# SCH_Creality_k1c_2026-01-29.net
KiCad netlist of a schematic drawn in EasyEDA
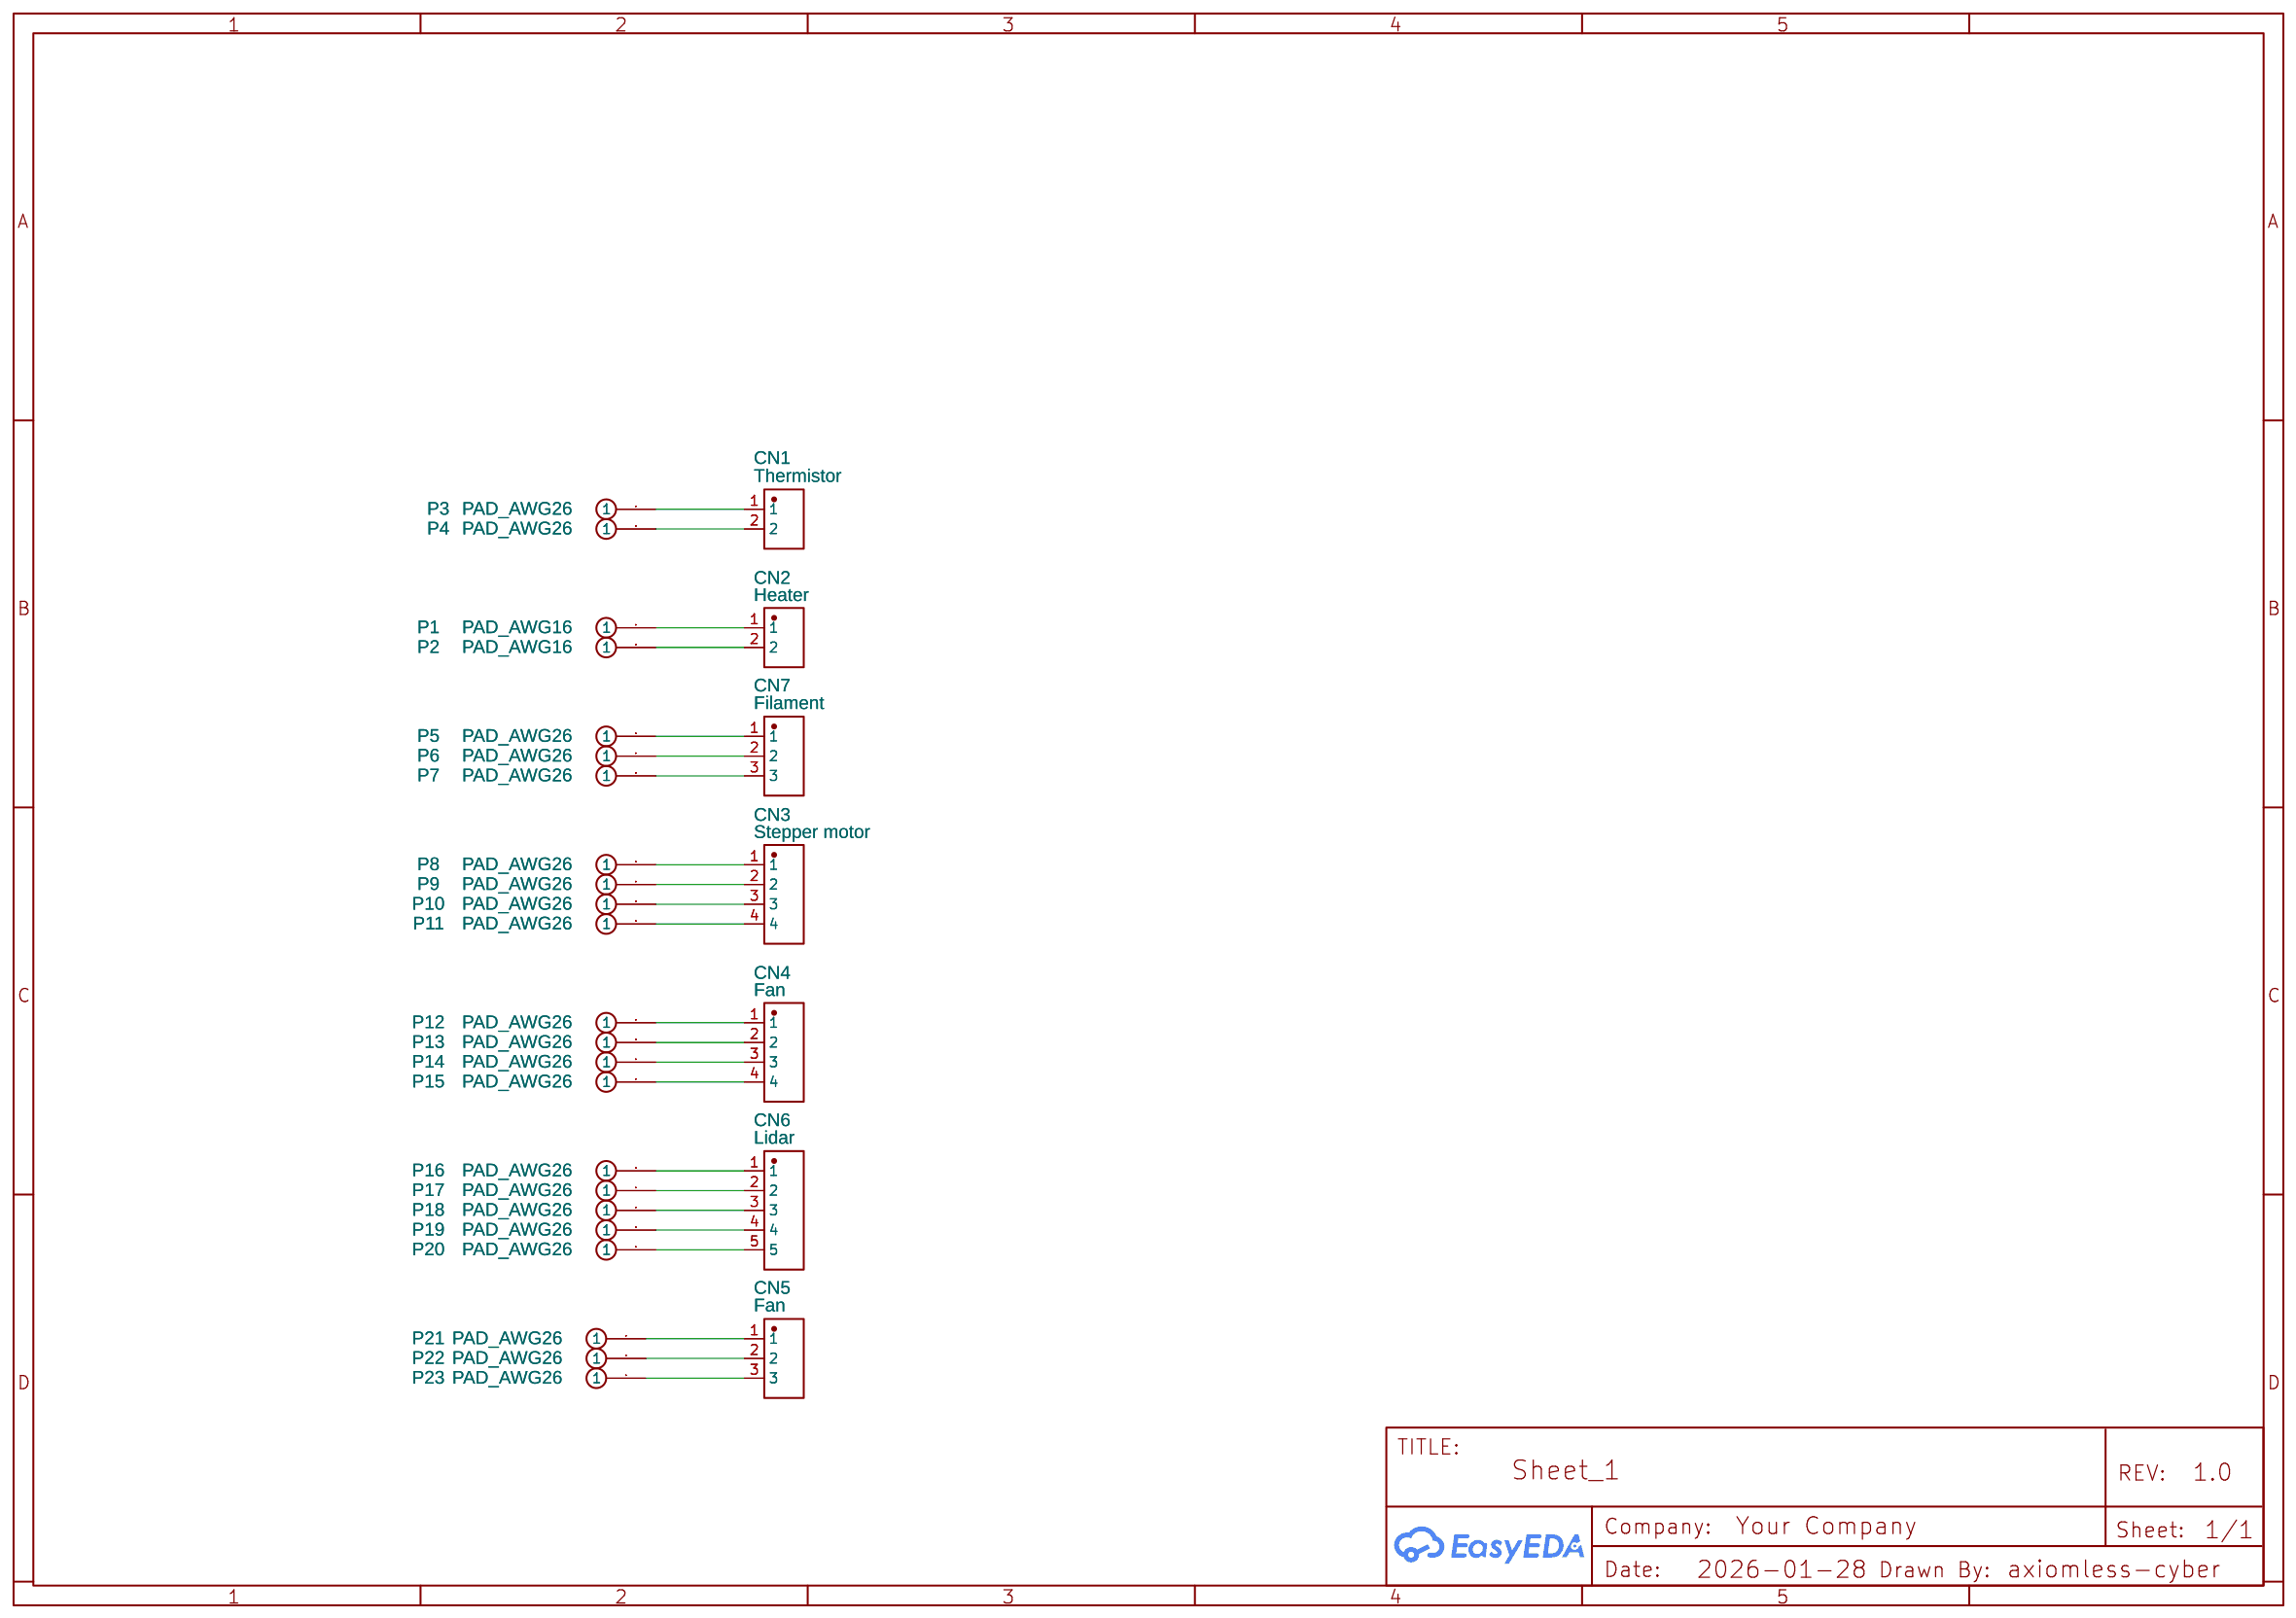
[diagram p0: schematic sheet]

(export (version "E")
  (design (tool "Eeschema 10.0.6"))
  (components
    (comp (ref "CN1")
      (value "Thermistor")
      (fields
        (field (name "Manufacturer Part") "WAFER-HY2.0-2PZZ-Y62")
        (field (name "Manufacturer") "XUNPU(讯普)")
      )
      (libsource (lib "") (part "WAFER-HY2.0-2PZZ-Y62"))
    )
    (comp (ref "CN2")
      (value "Heater")
      (fields (field (name "Manufacturer Part") "HX XHB2.54-2A") (field (name "Manufacturer") "hanxia(韩下)"))
      (libsource (lib "") (part "HX XHB2.54-2A"))
    )
    (comp (ref "CN3")
      (value "Stepper motor")
      (fields
        (field (name "Manufacturer Part") "ZX-MX1.25-4PZZ-Y")
        (field (name "Manufacturer") "Megastar(兆星)")
      )
      (libsource (lib "") (part "ZX-MX1.25-4PZZ-Y"))
    )
    (comp (ref "CN4")
      (value "Fan")
      (fields
        (field (name "Manufacturer Part") "ZX-MX1.25-4PZZ-Y")
        (field (name "Manufacturer") "Megastar(兆星)")
      )
      (libsource (lib "") (part "ZX-MX1.25-4PZZ-Y"))
    )
    (comp (ref "CN5")
      (value "Fan")
      (fields
        (field (name "Manufacturer Part") "BX-MX1.25-3PWZ-Y")
        (field (name "Manufacturer") "Bossie(博锡)")
      )
      (libsource (lib "") (part "BX-MX1.25-3PWZ-Y"))
    )
    (comp (ref "CN6")
      (value "Lidar")
      (fields
        (field (name "Manufacturer Part") "ZX-MX1.25-5PWZ-Y")
        (field (name "Manufacturer") "Megastar(兆星)")
      )
      (libsource (lib "") (part "ZX-MX1.25-5PWZ-Y"))
    )
    (comp (ref "CN7")
      (value "Filament")
      (fields
        (field (name "Manufacturer Part") "ZX-MX1.25-3PZZ-Y")
        (field (name "Manufacturer") "Megastar(兆星)")
      )
      (libsource (lib "") (part "ZX-MX1.25-3PZZ-Y"))
    )
    (comp (ref "P1") (value "PAD_AWG16") (libsource (lib "") (part "PAD_AWG16")))
    (comp (ref "P2") (value "PAD_AWG16") (libsource (lib "") (part "PAD_AWG16")))
    (comp (ref "P3") (value "PAD_AWG26") (libsource (lib "") (part "PAD_AWG26")))
    (comp (ref "P4") (value "PAD_AWG26") (libsource (lib "") (part "PAD_AWG26")))
    (comp (ref "P5") (value "PAD_AWG26") (libsource (lib "") (part "PAD_AWG26")))
    (comp (ref "P6") (value "PAD_AWG26") (libsource (lib "") (part "PAD_AWG26")))
    (comp (ref "P7") (value "PAD_AWG26") (libsource (lib "") (part "PAD_AWG26")))
    (comp (ref "P8") (value "PAD_AWG26") (libsource (lib "") (part "PAD_AWG26")))
    (comp (ref "P9") (value "PAD_AWG26") (libsource (lib "") (part "PAD_AWG26")))
    (comp (ref "P10") (value "PAD_AWG26") (libsource (lib "") (part "PAD_AWG26")))
    (comp (ref "P11") (value "PAD_AWG26") (libsource (lib "") (part "PAD_AWG26")))
    (comp (ref "P12") (value "PAD_AWG26") (libsource (lib "") (part "PAD_AWG26")))
    (comp (ref "P13") (value "PAD_AWG26") (libsource (lib "") (part "PAD_AWG26")))
    (comp (ref "P14") (value "PAD_AWG26") (libsource (lib "") (part "PAD_AWG26")))
    (comp (ref "P15") (value "PAD_AWG26") (libsource (lib "") (part "PAD_AWG26")))
    (comp (ref "P16") (value "PAD_AWG26") (libsource (lib "") (part "PAD_AWG26")))
    (comp (ref "P17") (value "PAD_AWG26") (libsource (lib "") (part "PAD_AWG26")))
    (comp (ref "P18") (value "PAD_AWG26") (libsource (lib "") (part "PAD_AWG26")))
    (comp (ref "P19") (value "PAD_AWG26") (libsource (lib "") (part "PAD_AWG26")))
    (comp (ref "P20") (value "PAD_AWG26") (libsource (lib "") (part "PAD_AWG26")))
    (comp (ref "P21") (value "PAD_AWG26") (libsource (lib "") (part "PAD_AWG26")))
    (comp (ref "P22") (value "PAD_AWG26") (libsource (lib "") (part "PAD_AWG26")))
    (comp (ref "P23") (value "PAD_AWG26") (libsource (lib "") (part "PAD_AWG26")))
  )
  (nets
    (net (code "1") (name "Net-(CN1-Pad1)") (class "Default")
      (node (ref "CN1") (pin "1") (pinfunction "1_1") (pintype "unspecified"))
      (node (ref "P3") (pin "1") (pinfunction "1_1") (pintype "unspecified"))
    )
    (net (code "2") (name "Net-(CN1-Pad2)") (class "Default")
      (node (ref "CN1") (pin "2") (pinfunction "2_2") (pintype "unspecified"))
      (node (ref "P4") (pin "1") (pinfunction "1_1") (pintype "unspecified"))
    )
    (net (code "3") (name "Net-(CN2-Pad1)") (class "Default")
      (node (ref "CN2") (pin "1") (pinfunction "1_1") (pintype "unspecified"))
      (node (ref "P1") (pin "1") (pinfunction "1_1") (pintype "unspecified"))
    )
    (net (code "4") (name "Net-(CN2-Pad2)") (class "Default")
      (node (ref "CN2") (pin "2") (pinfunction "2_2") (pintype "unspecified"))
      (node (ref "P2") (pin "1") (pinfunction "1_1") (pintype "unspecified"))
    )
    (net (code "5") (name "Net-(CN3-Pad1)") (class "Default")
      (node (ref "CN3") (pin "1") (pinfunction "1_1") (pintype "unspecified"))
      (node (ref "P8") (pin "1") (pinfunction "1_1") (pintype "unspecified"))
    )
    (net (code "6") (name "Net-(CN3-Pad2)") (class "Default")
      (node (ref "CN3") (pin "2") (pinfunction "2_2") (pintype "unspecified"))
      (node (ref "P9") (pin "1") (pinfunction "1_1") (pintype "unspecified"))
    )
    (net (code "7") (name "Net-(CN3-Pad3)") (class "Default")
      (node (ref "CN3") (pin "3") (pinfunction "3_3") (pintype "unspecified"))
      (node (ref "P10") (pin "1") (pinfunction "1_1") (pintype "unspecified"))
    )
    (net (code "8") (name "Net-(CN3-Pad4)") (class "Default")
      (node (ref "CN3") (pin "4") (pinfunction "4_4") (pintype "unspecified"))
      (node (ref "P11") (pin "1") (pinfunction "1_1") (pintype "unspecified"))
    )
    (net (code "9") (name "Net-(CN4-Pad1)") (class "Default")
      (node (ref "CN4") (pin "1") (pinfunction "1_1") (pintype "unspecified"))
      (node (ref "P12") (pin "1") (pinfunction "1_1") (pintype "unspecified"))
    )
    (net (code "10") (name "Net-(CN4-Pad2)") (class "Default")
      (node (ref "CN4") (pin "2") (pinfunction "2_2") (pintype "unspecified"))
      (node (ref "P13") (pin "1") (pinfunction "1_1") (pintype "unspecified"))
    )
    (net (code "11") (name "Net-(CN4-Pad3)") (class "Default")
      (node (ref "CN4") (pin "3") (pinfunction "3_3") (pintype "unspecified"))
      (node (ref "P14") (pin "1") (pinfunction "1_1") (pintype "unspecified"))
    )
    (net (code "12") (name "Net-(CN4-Pad4)") (class "Default")
      (node (ref "CN4") (pin "4") (pinfunction "4_4") (pintype "unspecified"))
      (node (ref "P15") (pin "1") (pinfunction "1_1") (pintype "unspecified"))
    )
    (net (code "13") (name "Net-(CN5-Pad1)") (class "Default")
      (node (ref "CN5") (pin "1") (pinfunction "1_1") (pintype "unspecified"))
      (node (ref "P21") (pin "1") (pinfunction "1_1") (pintype "unspecified"))
    )
    (net (code "14") (name "Net-(CN5-Pad2)") (class "Default")
      (node (ref "CN5") (pin "2") (pinfunction "2_2") (pintype "unspecified"))
      (node (ref "P22") (pin "1") (pinfunction "1_1") (pintype "unspecified"))
    )
    (net (code "15") (name "Net-(CN5-Pad3)") (class "Default")
      (node (ref "CN5") (pin "3") (pinfunction "3_3") (pintype "unspecified"))
      (node (ref "P23") (pin "1") (pinfunction "1_1") (pintype "unspecified"))
    )
    (net (code "16") (name "Net-(CN6-Pad1)") (class "Default")
      (node (ref "CN6") (pin "1") (pinfunction "1_1") (pintype "unspecified"))
      (node (ref "P16") (pin "1") (pinfunction "1_1") (pintype "unspecified"))
    )
    (net (code "17") (name "Net-(CN6-Pad2)") (class "Default")
      (node (ref "CN6") (pin "2") (pinfunction "2_2") (pintype "unspecified"))
      (node (ref "P17") (pin "1") (pinfunction "1_1") (pintype "unspecified"))
    )
    (net (code "18") (name "Net-(CN6-Pad3)") (class "Default")
      (node (ref "CN6") (pin "3") (pinfunction "3_3") (pintype "unspecified"))
      (node (ref "P18") (pin "1") (pinfunction "1_1") (pintype "unspecified"))
    )
    (net (code "19") (name "Net-(CN6-Pad4)") (class "Default")
      (node (ref "CN6") (pin "4") (pinfunction "4_4") (pintype "unspecified"))
      (node (ref "P19") (pin "1") (pinfunction "1_1") (pintype "unspecified"))
    )
    (net (code "20") (name "Net-(CN6-Pad5)") (class "Default")
      (node (ref "CN6") (pin "5") (pinfunction "5_5") (pintype "unspecified"))
      (node (ref "P20") (pin "1") (pinfunction "1_1") (pintype "unspecified"))
    )
    (net (code "21") (name "Net-(CN7-Pad1)") (class "Default")
      (node (ref "CN7") (pin "1") (pinfunction "1_1") (pintype "unspecified"))
      (node (ref "P5") (pin "1") (pinfunction "1_1") (pintype "unspecified"))
    )
    (net (code "22") (name "Net-(CN7-Pad2)") (class "Default")
      (node (ref "CN7") (pin "2") (pinfunction "2_2") (pintype "unspecified"))
      (node (ref "P6") (pin "1") (pinfunction "1_1") (pintype "unspecified"))
    )
    (net (code "23") (name "Net-(CN7-Pad3)") (class "Default")
      (node (ref "CN7") (pin "3") (pinfunction "3_3") (pintype "unspecified"))
      (node (ref "P7") (pin "1") (pinfunction "1_1") (pintype "unspecified"))
    )
  )
)
